# ArcadeJoystick.net
KiCad netlist of a schematic drawn in Altium Designer
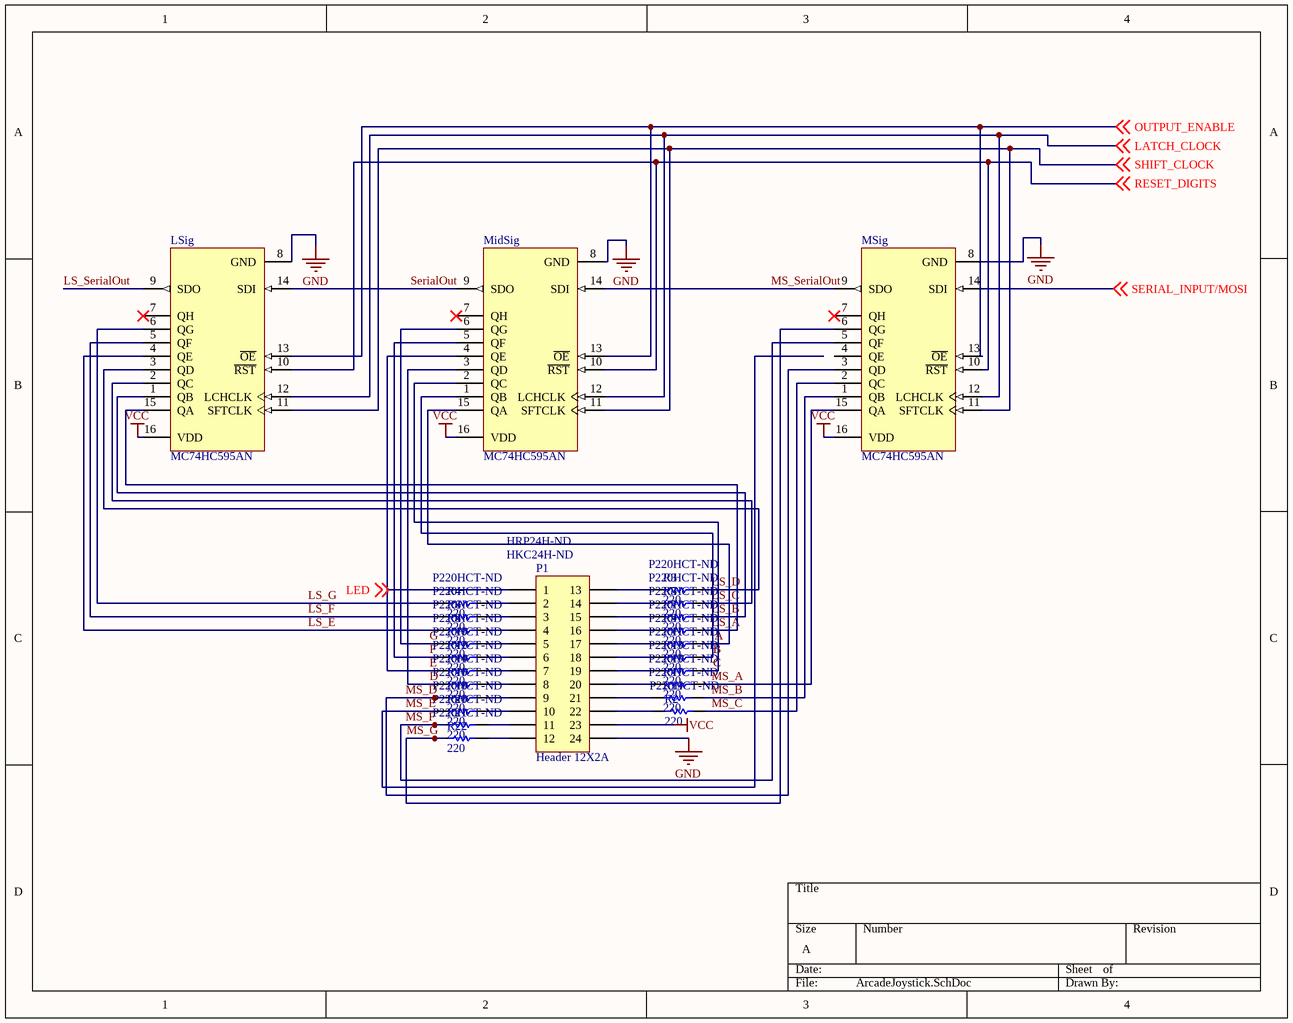
[diagram p0: ArcadeJoystick.SchDoc]

(export (version "E")
  (design (tool "Eeschema 10.0.6"))
  (components
    (comp (ref "LSig")
      (value "MC74HC595AN")
      (footprint "648-08")
      (description "8-Bit Serial-Input/Serial or Prallel-Output Shift Register with Latched 3-State Outputs")
      (fields (field (name "PUBLISHER") "Altium Limited"))
      (libsource (lib "ON Semi Logic Register") (part "MC74HC595AN"))
    )
    (comp (ref "MidSig")
      (value "MC74HC595AN")
      (footprint "648-08")
      (description "8-Bit Serial-Input/Serial or Prallel-Output Shift Register with Latched 3-State Outputs")
      (fields (field (name "PUBLISHER") "Altium Limited"))
      (libsource (lib "ON Semi Logic Register") (part "MC74HC595AN"))
    )
    (comp (ref "MSig")
      (value "MC74HC595AN")
      (footprint "648-08")
      (description "8-Bit Serial-Input/Serial or Prallel-Output Shift Register with Latched 3-State Outputs")
      (fields (field (name "PUBLISHER") "Altium Limited"))
      (libsource (lib "ON Semi Logic Register") (part "MC74HC595AN"))
    )
    (comp (ref "P1")
      (value "Header 12X2A")
      (footprint "HDR2X12_CEN")
      (description "Header, 12-Pin, Dual row")
      (fields
        (field (name "SUPPLIER PART NUMBER 1") "HKC24H-ND")
        (field (name "SUPPLIER PART NUMBER 2") "HRP24H-ND")
        (field (name "PUBLISHER") "Altium Limited")
      )
      (libsource (lib "Miscellaneous Connectors") (part "Header 12X2A"))
    )
    (comp (ref "R2")
      (value "220")
      (footprint "1608[0603]")
      (description "Semiconductor Resistor")
      (fields
        (field (name "SUPPLIER PART NUMBER 1") "P220HCT-ND")
        (field (name "Comment") "Res Semi")
        (field (name "PUBLISHER") "Altium Limited")
      )
      (libsource (lib "Miscellaneous Devices") (part "Res Semi"))
    )
    (comp (ref "R3")
      (value "220")
      (footprint "1608[0603]")
      (description "Semiconductor Resistor")
      (fields
        (field (name "SUPPLIER PART NUMBER 1") "P220HCT-ND")
        (field (name "Comment") "Res Semi")
        (field (name "PUBLISHER") "Altium Limited")
      )
      (libsource (lib "Miscellaneous Devices") (part "Res Semi"))
    )
    (comp (ref "R4")
      (value "220")
      (footprint "1608[0603]")
      (description "Semiconductor Resistor")
      (fields
        (field (name "SUPPLIER PART NUMBER 1") "P220HCT-ND")
        (field (name "Comment") "Res Semi")
        (field (name "PUBLISHER") "Altium Limited")
      )
      (libsource (lib "Miscellaneous Devices") (part "Res Semi"))
    )
    (comp (ref "R5")
      (value "220")
      (footprint "1608[0603]")
      (description "Semiconductor Resistor")
      (fields
        (field (name "SUPPLIER PART NUMBER 1") "P220HCT-ND")
        (field (name "Comment") "Res Semi")
        (field (name "PUBLISHER") "Altium Limited")
      )
      (libsource (lib "Miscellaneous Devices") (part "Res Semi"))
    )
    (comp (ref "R6")
      (value "220")
      (footprint "1608[0603]")
      (description "Semiconductor Resistor")
      (fields
        (field (name "SUPPLIER PART NUMBER 1") "P220HCT-ND")
        (field (name "Comment") "Res Semi")
        (field (name "PUBLISHER") "Altium Limited")
      )
      (libsource (lib "Miscellaneous Devices") (part "Res Semi"))
    )
    (comp (ref "R7")
      (value "220")
      (footprint "1608[0603]")
      (description "Semiconductor Resistor")
      (fields
        (field (name "SUPPLIER PART NUMBER 1") "P220HCT-ND")
        (field (name "Comment") "Res Semi")
        (field (name "PUBLISHER") "Altium Limited")
      )
      (libsource (lib "Miscellaneous Devices") (part "Res Semi"))
    )
    (comp (ref "R8")
      (value "220")
      (footprint "1608[0603]")
      (description "Semiconductor Resistor")
      (fields
        (field (name "SUPPLIER PART NUMBER 1") "P220HCT-ND")
        (field (name "Comment") "Res Semi")
        (field (name "PUBLISHER") "Altium Limited")
      )
      (libsource (lib "Miscellaneous Devices") (part "Res Semi"))
    )
    (comp (ref "R9")
      (value "220")
      (footprint "1608[0603]")
      (description "Semiconductor Resistor")
      (fields
        (field (name "SUPPLIER PART NUMBER 1") "P220HCT-ND")
        (field (name "Comment") "Res Semi")
        (field (name "PUBLISHER") "Altium Limited")
      )
      (libsource (lib "Miscellaneous Devices") (part "Res Semi"))
    )
    (comp (ref "R10")
      (value "220")
      (footprint "1608[0603]")
      (description "Semiconductor Resistor")
      (fields
        (field (name "SUPPLIER PART NUMBER 1") "P220HCT-ND")
        (field (name "Comment") "Res Semi")
        (field (name "PUBLISHER") "Altium Limited")
      )
      (libsource (lib "Miscellaneous Devices") (part "Res Semi"))
    )
    (comp (ref "R11")
      (value "220")
      (footprint "1608[0603]")
      (description "Semiconductor Resistor")
      (fields
        (field (name "SUPPLIER PART NUMBER 1") "P220HCT-ND")
        (field (name "Comment") "Res Semi")
        (field (name "PUBLISHER") "Altium Limited")
      )
      (libsource (lib "Miscellaneous Devices") (part "Res Semi"))
    )
    (comp (ref "R12")
      (value "220")
      (footprint "1608[0603]")
      (description "Semiconductor Resistor")
      (fields
        (field (name "SUPPLIER PART NUMBER 1") "P220HCT-ND")
        (field (name "Comment") "Res Semi")
        (field (name "PUBLISHER") "Altium Limited")
      )
      (libsource (lib "Miscellaneous Devices") (part "Res Semi"))
    )
    (comp (ref "R13")
      (value "220")
      (footprint "1608[0603]")
      (description "Semiconductor Resistor")
      (fields
        (field (name "SUPPLIER PART NUMBER 1") "P220HCT-ND")
        (field (name "Comment") "Res Semi")
        (field (name "PUBLISHER") "Altium Limited")
      )
      (libsource (lib "Miscellaneous Devices") (part "Res Semi"))
    )
    (comp (ref "R14")
      (value "220")
      (footprint "1608[0603]")
      (description "Semiconductor Resistor")
      (fields
        (field (name "SUPPLIER PART NUMBER 1") "P220HCT-ND")
        (field (name "Comment") "Res Semi")
        (field (name "PUBLISHER") "Altium Limited")
      )
      (libsource (lib "Miscellaneous Devices") (part "Res Semi"))
    )
    (comp (ref "R15")
      (value "220")
      (footprint "1608[0603]")
      (description "Semiconductor Resistor")
      (fields
        (field (name "SUPPLIER PART NUMBER 1") "P220HCT-ND")
        (field (name "Comment") "Res Semi")
        (field (name "PUBLISHER") "Altium Limited")
      )
      (libsource (lib "Miscellaneous Devices") (part "Res Semi"))
    )
    (comp (ref "R16")
      (value "220")
      (footprint "1608[0603]")
      (description "Semiconductor Resistor")
      (fields
        (field (name "SUPPLIER PART NUMBER 1") "P220HCT-ND")
        (field (name "Comment") "Res Semi")
        (field (name "PUBLISHER") "Altium Limited")
      )
      (libsource (lib "Miscellaneous Devices") (part "Res Semi"))
    )
    (comp (ref "R17")
      (value "220")
      (footprint "1608[0603]")
      (description "Semiconductor Resistor")
      (fields
        (field (name "SUPPLIER PART NUMBER 1") "P220HCT-ND")
        (field (name "Comment") "Res Semi")
        (field (name "PUBLISHER") "Altium Limited")
      )
      (libsource (lib "Miscellaneous Devices") (part "Res Semi"))
    )
    (comp (ref "R18")
      (value "220")
      (footprint "1608[0603]")
      (description "Semiconductor Resistor")
      (fields
        (field (name "SUPPLIER PART NUMBER 1") "P220HCT-ND")
        (field (name "Comment") "Res Semi")
        (field (name "PUBLISHER") "Altium Limited")
      )
      (libsource (lib "Miscellaneous Devices") (part "Res Semi"))
    )
    (comp (ref "R19")
      (value "220")
      (footprint "1608[0603]")
      (description "Semiconductor Resistor")
      (fields
        (field (name "SUPPLIER PART NUMBER 1") "P220HCT-ND")
        (field (name "Comment") "Res Semi")
        (field (name "PUBLISHER") "Altium Limited")
      )
      (libsource (lib "Miscellaneous Devices") (part "Res Semi"))
    )
    (comp (ref "R20")
      (value "220")
      (footprint "1608[0603]")
      (description "Semiconductor Resistor")
      (fields
        (field (name "SUPPLIER PART NUMBER 1") "P220HCT-ND")
        (field (name "Comment") "Res Semi")
        (field (name "PUBLISHER") "Altium Limited")
      )
      (libsource (lib "Miscellaneous Devices") (part "Res Semi"))
    )
    (comp (ref "R21")
      (value "220")
      (footprint "1608[0603]")
      (description "Semiconductor Resistor")
      (fields
        (field (name "SUPPLIER PART NUMBER 1") "P220HCT-ND")
        (field (name "Comment") "Res Semi")
        (field (name "PUBLISHER") "Altium Limited")
      )
      (libsource (lib "Miscellaneous Devices") (part "Res Semi"))
    )
    (comp (ref "R22")
      (value "220")
      (footprint "1608[0603]")
      (description "Semiconductor Resistor")
      (fields
        (field (name "SUPPLIER PART NUMBER 1") "P220HCT-ND")
        (field (name "Comment") "Res Semi")
        (field (name "PUBLISHER") "Altium Limited")
      )
      (libsource (lib "Miscellaneous Devices") (part "Res Semi"))
    )
  )
  (nets
    (net (code "1") (name "/A") (class "Default")
      (node (ref "MidSig") (pin "15") (pinfunction "QA_15") (pintype "tri_state"))
      (node (ref "R11") (pin "2") (pinfunction "2_2") (pintype "passive"))
    )
    (net (code "2") (name "/B") (class "Default")
      (node (ref "MidSig") (pin "1") (pinfunction "QB_1") (pintype "tri_state"))
      (node (ref "R13") (pin "2") (pinfunction "2_2") (pintype "passive"))
    )
    (net (code "3") (name "/C") (class "Default")
      (node (ref "MidSig") (pin "2") (pinfunction "QC_2") (pintype "tri_state"))
      (node (ref "R15") (pin "2") (pinfunction "2_2") (pintype "passive"))
    )
    (net (code "4") (name "/D") (class "Default")
      (node (ref "MidSig") (pin "3") (pinfunction "QD_3") (pintype "tri_state"))
      (node (ref "R16") (pin "1") (pinfunction "1_1") (pintype "passive"))
    )
    (net (code "5") (name "/E") (class "Default")
      (node (ref "MidSig") (pin "4") (pinfunction "QE_4") (pintype "tri_state"))
      (node (ref "R14") (pin "1") (pinfunction "1_1") (pintype "passive"))
    )
    (net (code "6") (name "/F") (class "Default")
      (node (ref "MidSig") (pin "5") (pinfunction "QF_5") (pintype "tri_state"))
      (node (ref "R12") (pin "1") (pinfunction "1_1") (pintype "passive"))
    )
    (net (code "7") (name "/G") (class "Default")
      (node (ref "MidSig") (pin "6") (pinfunction "QG_6") (pintype "tri_state"))
      (node (ref "R10") (pin "1") (pinfunction "1_1") (pintype "passive"))
    )
    (net (code "8") (name "/LS_A") (class "Default")
      (node (ref "LSig") (pin "15") (pinfunction "QA_15") (pintype "tri_state"))
      (node (ref "R9") (pin "2") (pinfunction "2_2") (pintype "passive"))
    )
    (net (code "9") (name "/LS_B") (class "Default")
      (node (ref "LSig") (pin "1") (pinfunction "QB_1") (pintype "tri_state"))
      (node (ref "R7") (pin "2") (pinfunction "2_2") (pintype "passive"))
    )
    (net (code "10") (name "/LS_C") (class "Default")
      (node (ref "LSig") (pin "2") (pinfunction "QC_2") (pintype "tri_state"))
      (node (ref "R5") (pin "2") (pinfunction "2_2") (pintype "passive"))
    )
    (net (code "11") (name "/LS_D") (class "Default")
      (node (ref "LSig") (pin "3") (pinfunction "QD_3") (pintype "tri_state"))
      (node (ref "R3") (pin "2") (pinfunction "2_2") (pintype "passive"))
    )
    (net (code "12") (name "/LS_E") (class "Default")
      (node (ref "LSig") (pin "4") (pinfunction "QE_4") (pintype "tri_state"))
      (node (ref "R8") (pin "1") (pinfunction "1_1") (pintype "passive"))
    )
    (net (code "13") (name "/LS_F") (class "Default")
      (node (ref "LSig") (pin "5") (pinfunction "QF_5") (pintype "tri_state"))
      (node (ref "R6") (pin "1") (pinfunction "1_1") (pintype "passive"))
    )
    (net (code "14") (name "/LS_G") (class "Default")
      (node (ref "LSig") (pin "6") (pinfunction "QG_6") (pintype "tri_state"))
      (node (ref "R4") (pin "1") (pinfunction "1_1") (pintype "passive"))
    )
    (net (code "15") (name "/LS_SerialOut") (class "Default")
      (node (ref "LSig") (pin "9") (pinfunction "SDO_9") (pintype "output"))
    )
    (net (code "16") (name "/MS_A") (class "Default")
      (node (ref "MSig") (pin "15") (pinfunction "QA_15") (pintype "tri_state"))
      (node (ref "R17") (pin "2") (pinfunction "2_2") (pintype "passive"))
    )
    (net (code "17") (name "/MS_B") (class "Default")
      (node (ref "MSig") (pin "1") (pinfunction "QB_1") (pintype "tri_state"))
      (node (ref "R19") (pin "2") (pinfunction "2_2") (pintype "passive"))
    )
    (net (code "18") (name "/MS_C") (class "Default")
      (node (ref "MSig") (pin "2") (pinfunction "QC_2") (pintype "tri_state"))
      (node (ref "R2") (pin "2") (pinfunction "2_2") (pintype "passive"))
    )
    (net (code "19") (name "/MS_D") (class "Default")
      (node (ref "MSig") (pin "3") (pinfunction "QD_3") (pintype "tri_state"))
      (node (ref "R18") (pin "1") (pinfunction "1_1") (pintype "passive"))
    )
    (net (code "20") (name "/MS_E") (class "Default")
      (node (ref "R20") (pin "1") (pinfunction "1_1") (pintype "passive"))
    )
    (net (code "21") (name "/MS_F") (class "Default")
      (node (ref "MSig") (pin "5") (pinfunction "QF_5") (pintype "tri_state"))
      (node (ref "R21") (pin "1") (pinfunction "1_1") (pintype "passive"))
    )
    (net (code "22") (name "/MS_G") (class "Default")
      (node (ref "MSig") (pin "6") (pinfunction "QG_6") (pintype "tri_state"))
      (node (ref "R22") (pin "1") (pinfunction "1_1") (pintype "passive"))
    )
    (net (code "23") (name "/MS_SerialOut") (class "Default")
      (node (ref "MSig") (pin "9") (pinfunction "SDO_9") (pintype "output"))
      (node (ref "MidSig") (pin "14") (pinfunction "SDI_14") (pintype "input"))
    )
    (net (code "24") (name "/SerialOut") (class "Default")
      (node (ref "LSig") (pin "14") (pinfunction "SDI_14") (pintype "input"))
      (node (ref "MidSig") (pin "9") (pinfunction "SDO_9") (pintype "output"))
    )
    (net (code "25") (name "GND") (class "Default")
      (node (ref "LSig") (pin "8") (pinfunction "GND_8") (pintype "power_in"))
      (node (ref "MSig") (pin "8") (pinfunction "GND_8") (pintype "power_in"))
      (node (ref "MidSig") (pin "8") (pinfunction "GND_8") (pintype "power_in"))
      (node (ref "P1") (pin "24") (pinfunction "24_24") (pintype "passive"))
    )
    (net (code "26") (name "LATCH_CLOCK") (class "Default")
      (node (ref "LSig") (pin "12") (pinfunction "LCHCLK_12") (pintype "input"))
      (node (ref "MSig") (pin "12") (pinfunction "LCHCLK_12") (pintype "input"))
      (node (ref "MidSig") (pin "12") (pinfunction "LCHCLK_12") (pintype "input"))
    )
    (net (code "27") (name "LED") (class "Default")
      (node (ref "P1") (pin "1") (pinfunction "1_1") (pintype "passive"))
    )
    (net (code "28") (name "Net-(P1-Pad2)") (class "Default")
      (node (ref "P1") (pin "2") (pinfunction "2_2") (pintype "passive"))
      (node (ref "R4") (pin "2") (pinfunction "2_2") (pintype "passive"))
    )
    (net (code "29") (name "Net-(P1-Pad3)") (class "Default")
      (node (ref "P1") (pin "3") (pinfunction "3_3") (pintype "passive"))
      (node (ref "R6") (pin "2") (pinfunction "2_2") (pintype "passive"))
    )
    (net (code "30") (name "Net-(P1-Pad4)") (class "Default")
      (node (ref "P1") (pin "4") (pinfunction "4_4") (pintype "passive"))
      (node (ref "R8") (pin "2") (pinfunction "2_2") (pintype "passive"))
    )
    (net (code "31") (name "Net-(P1-Pad5)") (class "Default")
      (node (ref "P1") (pin "5") (pinfunction "5_5") (pintype "passive"))
      (node (ref "R10") (pin "2") (pinfunction "2_2") (pintype "passive"))
    )
    (net (code "32") (name "Net-(P1-Pad6)") (class "Default")
      (node (ref "P1") (pin "6") (pinfunction "6_6") (pintype "passive"))
      (node (ref "R12") (pin "2") (pinfunction "2_2") (pintype "passive"))
    )
    (net (code "33") (name "Net-(P1-Pad7)") (class "Default")
      (node (ref "P1") (pin "7") (pinfunction "7_7") (pintype "passive"))
      (node (ref "R14") (pin "2") (pinfunction "2_2") (pintype "passive"))
    )
    (net (code "34") (name "Net-(P1-Pad8)") (class "Default")
      (node (ref "P1") (pin "8") (pinfunction "8_8") (pintype "passive"))
      (node (ref "R16") (pin "2") (pinfunction "2_2") (pintype "passive"))
    )
    (net (code "35") (name "Net-(P1-Pad9)") (class "Default")
      (node (ref "P1") (pin "9") (pinfunction "9_9") (pintype "passive"))
      (node (ref "R18") (pin "2") (pinfunction "2_2") (pintype "passive"))
    )
    (net (code "36") (name "Net-(P1-Pad10)") (class "Default")
      (node (ref "P1") (pin "10") (pinfunction "10_10") (pintype "passive"))
      (node (ref "R20") (pin "2") (pinfunction "2_2") (pintype "passive"))
    )
    (net (code "37") (name "Net-(P1-Pad11)") (class "Default")
      (node (ref "P1") (pin "11") (pinfunction "11_11") (pintype "passive"))
      (node (ref "R21") (pin "2") (pinfunction "2_2") (pintype "passive"))
    )
    (net (code "38") (name "Net-(P1-Pad12)") (class "Default")
      (node (ref "P1") (pin "12") (pinfunction "12_12") (pintype "passive"))
      (node (ref "R22") (pin "2") (pinfunction "2_2") (pintype "passive"))
    )
    (net (code "39") (name "Net-(P1-Pad13)") (class "Default")
      (node (ref "P1") (pin "13") (pinfunction "13_13") (pintype "passive"))
      (node (ref "R3") (pin "1") (pinfunction "1_1") (pintype "passive"))
    )
    (net (code "40") (name "Net-(P1-Pad14)") (class "Default")
      (node (ref "P1") (pin "14") (pinfunction "14_14") (pintype "passive"))
      (node (ref "R5") (pin "1") (pinfunction "1_1") (pintype "passive"))
    )
    (net (code "41") (name "Net-(P1-Pad15)") (class "Default")
      (node (ref "P1") (pin "15") (pinfunction "15_15") (pintype "passive"))
      (node (ref "R7") (pin "1") (pinfunction "1_1") (pintype "passive"))
    )
    (net (code "42") (name "Net-(P1-Pad16)") (class "Default")
      (node (ref "P1") (pin "16") (pinfunction "16_16") (pintype "passive"))
      (node (ref "R9") (pin "1") (pinfunction "1_1") (pintype "passive"))
    )
    (net (code "43") (name "Net-(P1-Pad17)") (class "Default")
      (node (ref "P1") (pin "17") (pinfunction "17_17") (pintype "passive"))
      (node (ref "R11") (pin "1") (pinfunction "1_1") (pintype "passive"))
    )
    (net (code "44") (name "Net-(P1-Pad18)") (class "Default")
      (node (ref "P1") (pin "18") (pinfunction "18_18") (pintype "passive"))
      (node (ref "R13") (pin "1") (pinfunction "1_1") (pintype "passive"))
    )
    (net (code "45") (name "Net-(P1-Pad19)") (class "Default")
      (node (ref "P1") (pin "19") (pinfunction "19_19") (pintype "passive"))
      (node (ref "R15") (pin "1") (pinfunction "1_1") (pintype "passive"))
    )
    (net (code "46") (name "Net-(P1-Pad20)") (class "Default")
      (node (ref "P1") (pin "20") (pinfunction "20_20") (pintype "passive"))
      (node (ref "R17") (pin "1") (pinfunction "1_1") (pintype "passive"))
    )
    (net (code "47") (name "Net-(P1-Pad21)") (class "Default")
      (node (ref "P1") (pin "21") (pinfunction "21_21") (pintype "passive"))
      (node (ref "R19") (pin "1") (pinfunction "1_1") (pintype "passive"))
    )
    (net (code "48") (name "Net-(P1-Pad22)") (class "Default")
      (node (ref "P1") (pin "22") (pinfunction "22_22") (pintype "passive"))
      (node (ref "R2") (pin "1") (pinfunction "1_1") (pintype "passive"))
    )
    (net (code "49") (name "OUTPUT_ENABLE") (class "Default")
      (node (ref "LSig") (pin "13") (pinfunction "~{OE}_13") (pintype "input"))
      (node (ref "MSig") (pin "13") (pinfunction "~{OE}_13") (pintype "input"))
      (node (ref "MidSig") (pin "13") (pinfunction "~{OE}_13") (pintype "input"))
    )
    (net (code "50") (name "RESET_DIGITS") (class "Default")
      (node (ref "LSig") (pin "10") (pinfunction "~{RST}_10") (pintype "input"))
      (node (ref "MSig") (pin "10") (pinfunction "~{RST}_10") (pintype "input"))
      (node (ref "MidSig") (pin "10") (pinfunction "~{RST}_10") (pintype "input"))
    )
    (net (code "51") (name "SERIAL_INPUT{slash}MOSI") (class "Default")
      (node (ref "MSig") (pin "14") (pinfunction "SDI_14") (pintype "input"))
    )
    (net (code "52") (name "SHIFT_CLOCK") (class "Default")
      (node (ref "LSig") (pin "11") (pinfunction "SFTCLK_11") (pintype "input"))
      (node (ref "MSig") (pin "11") (pinfunction "SFTCLK_11") (pintype "input"))
      (node (ref "MidSig") (pin "11") (pinfunction "SFTCLK_11") (pintype "input"))
    )
    (net (code "53") (name "VCC") (class "Default")
      (node (ref "LSig") (pin "16") (pinfunction "VDD_16") (pintype "power_in"))
      (node (ref "MSig") (pin "16") (pinfunction "VDD_16") (pintype "power_in"))
      (node (ref "MidSig") (pin "16") (pinfunction "VDD_16") (pintype "power_in"))
      (node (ref "P1") (pin "23") (pinfunction "23_23") (pintype "passive"))
    )
    (net (code "54") (name "unconnected-(LSig-QH-Pad7)") (class "Default")
      (node (ref "LSig") (pin "7") (pinfunction "QH_7") (pintype "tri_state+no_connect"))
    )
    (net (code "55") (name "unconnected-(MSig-QE-Pad4)") (class "Default")
      (node (ref "MSig") (pin "4") (pinfunction "QE_4") (pintype "tri_state"))
    )
    (net (code "56") (name "unconnected-(MSig-QH-Pad7)") (class "Default")
      (node (ref "MSig") (pin "7") (pinfunction "QH_7") (pintype "tri_state+no_connect"))
    )
    (net (code "57") (name "unconnected-(MidSig-QH-Pad7)") (class "Default")
      (node (ref "MidSig") (pin "7") (pinfunction "QH_7") (pintype "tri_state+no_connect"))
    )
  )
)
